# main.net
KiCad netlist of a schematic drawn in EAGLE
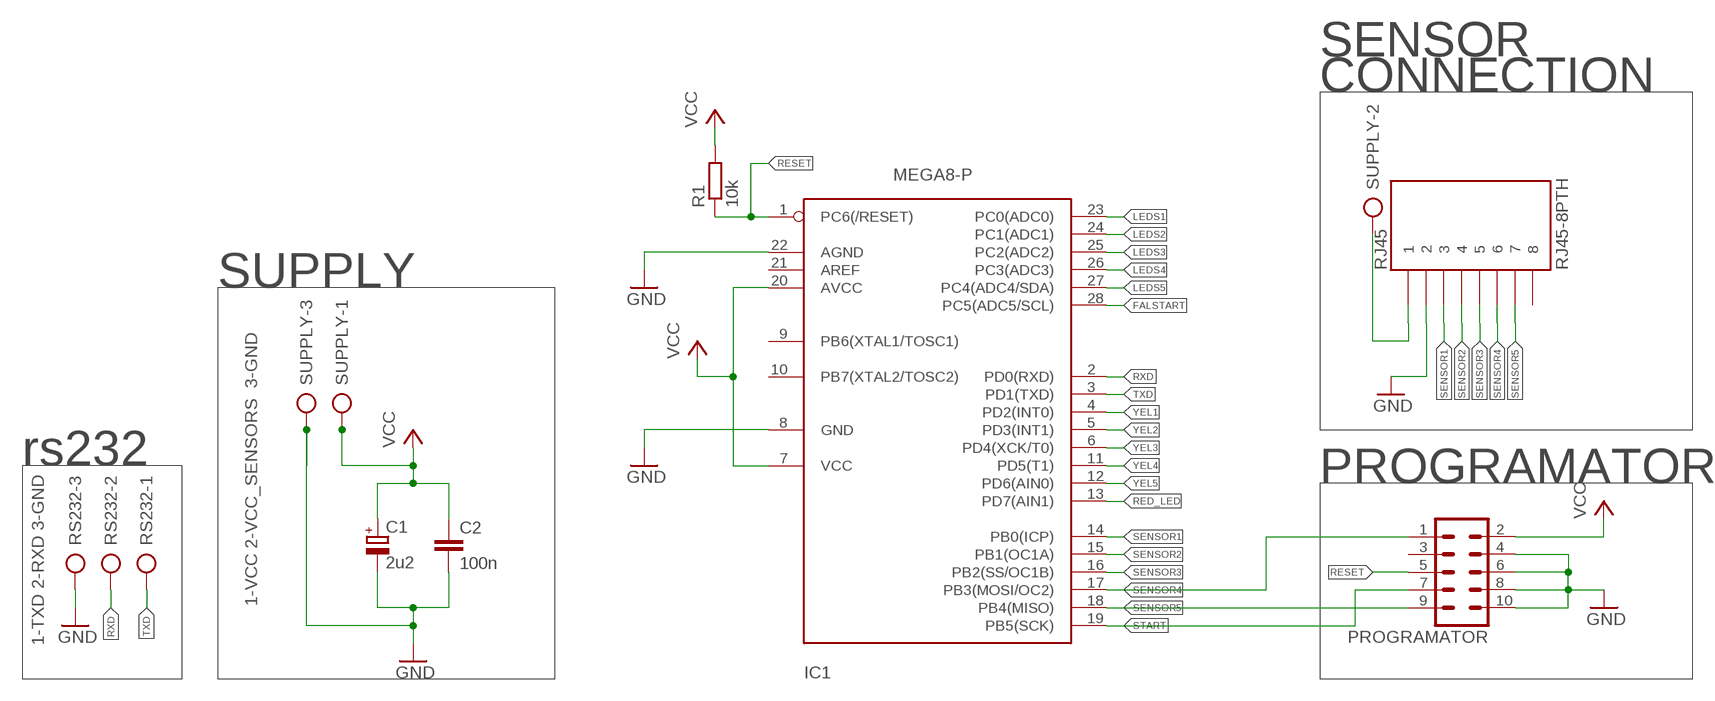
[diagram p0: schematic, sheet 1, part 1 of 2]
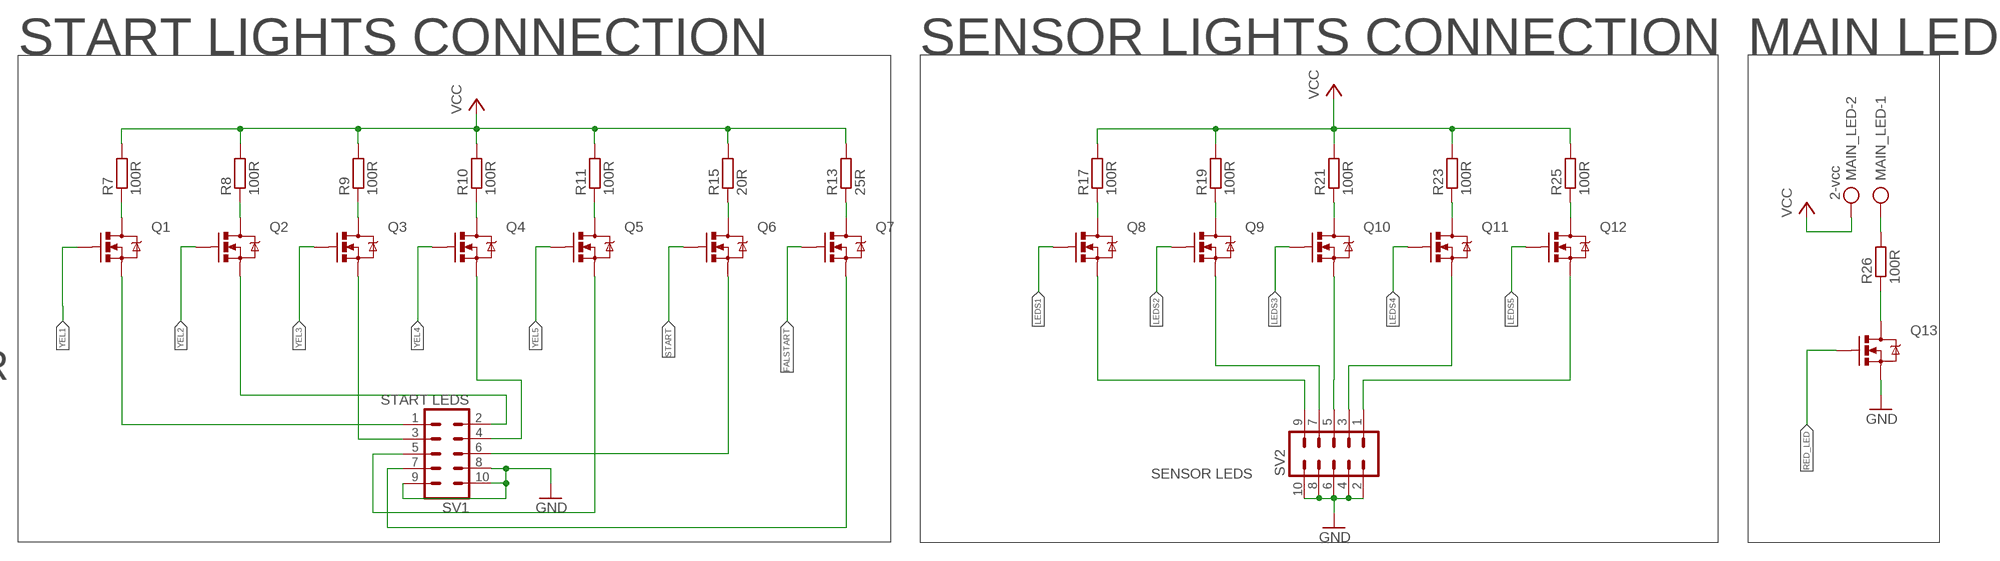
[diagram p1: schematic, sheet 1, part 2 of 2]

(export (version "E")
  (design (tool "Eeschema 10.0.6"))
  (components
    (comp (ref "C1")
      (value "2u2")
      (footprint "eagle-import:E2-5")
      (libsource (lib "eagle-import") (part "CPOL-EUE2-5"))
    )
    (comp (ref "C2")
      (value "100n")
      (footprint "eagle-import:C0805")
      (libsource (lib "eagle-import") (part "C-EUC0805"))
    )
    (comp (ref "IC1")
      (value "MEGA8-P")
      (footprint "eagle-import:DIL28-3")
      (libsource (lib "eagle-import") (part "MEGA8-P"))
    )
    (comp (ref "MAIN_LED")
      (value "2-vcc")
      (footprint "eagle-import:AK300_2")
      (libsource (lib "eagle-import") (part "AK300/2"))
    )
    (comp (ref "PROGRAMATOR")
      (value "ML10L")
      (footprint "eagle-import:ML10L")
      (libsource (lib "eagle-import") (part "ML10L"))
    )
    (comp (ref "Q1")
      (value "MOSFET-NCHANNEL2N7002PW")
      (footprint "eagle-import:SOT323")
      (libsource (lib "eagle-import") (part "MOSFET-NCHANNEL2N7002PW"))
    )
    (comp (ref "Q2")
      (value "MOSFET-NCHANNEL2N7002PW")
      (footprint "eagle-import:SOT323")
      (fields (field (name "PROD_ID") "TRANS-11151"))
      (libsource (lib "eagle-import") (part "MOSFET-NCHANNEL2N7002PW"))
    )
    (comp (ref "Q3")
      (value "MOSFET-NCHANNEL2N7002PW")
      (footprint "eagle-import:SOT323")
      (fields (field (name "PROD_ID") "TRANS-11151"))
      (libsource (lib "eagle-import") (part "MOSFET-NCHANNEL2N7002PW"))
    )
    (comp (ref "Q4")
      (value "MOSFET-NCHANNEL2N7002PW")
      (footprint "eagle-import:SOT323")
      (fields (field (name "PROD_ID") "TRANS-11151"))
      (libsource (lib "eagle-import") (part "MOSFET-NCHANNEL2N7002PW"))
    )
    (comp (ref "Q5")
      (value "MOSFET-NCHANNEL2N7002PW")
      (footprint "eagle-import:SOT323")
      (fields (field (name "PROD_ID") "TRANS-11151"))
      (libsource (lib "eagle-import") (part "MOSFET-NCHANNEL2N7002PW"))
    )
    (comp (ref "Q6")
      (value "MOSFET-NCHANNEL2N7002PW")
      (footprint "eagle-import:SOT323")
      (fields (field (name "PROD_ID") "TRANS-11151"))
      (libsource (lib "eagle-import") (part "MOSFET-NCHANNEL2N7002PW"))
    )
    (comp (ref "Q7")
      (value "MOSFET-NCHANNEL2N7002PW")
      (footprint "eagle-import:SOT323")
      (fields (field (name "PROD_ID") "TRANS-11151"))
      (libsource (lib "eagle-import") (part "MOSFET-NCHANNEL2N7002PW"))
    )
    (comp (ref "Q8")
      (value "MOSFET-NCHANNEL2N7002PW")
      (footprint "eagle-import:SOT323")
      (fields (field (name "PROD_ID") "TRANS-11151"))
      (libsource (lib "eagle-import") (part "MOSFET-NCHANNEL2N7002PW"))
    )
    (comp (ref "Q9")
      (value "MOSFET-NCHANNEL2N7002PW")
      (footprint "eagle-import:SOT323")
      (fields (field (name "PROD_ID") "TRANS-11151"))
      (libsource (lib "eagle-import") (part "MOSFET-NCHANNEL2N7002PW"))
    )
    (comp (ref "Q10")
      (value "MOSFET-NCHANNEL2N7002PW")
      (footprint "eagle-import:SOT323")
      (fields (field (name "PROD_ID") "TRANS-11151"))
      (libsource (lib "eagle-import") (part "MOSFET-NCHANNEL2N7002PW"))
    )
    (comp (ref "Q11")
      (value "MOSFET-NCHANNEL2N7002PW")
      (footprint "eagle-import:SOT323")
      (fields (field (name "PROD_ID") "TRANS-11151"))
      (libsource (lib "eagle-import") (part "MOSFET-NCHANNEL2N7002PW"))
    )
    (comp (ref "Q12")
      (value "MOSFET-NCHANNEL2N7002PW")
      (footprint "eagle-import:SOT323")
      (fields (field (name "PROD_ID") "TRANS-11151"))
      (libsource (lib "eagle-import") (part "MOSFET-NCHANNEL2N7002PW"))
    )
    (comp (ref "Q13")
      (value "MOSFET-NCHANNEL2N7002PW")
      (footprint "eagle-import:SOT323")
      (fields (field (name "PROD_ID") "TRANS-11151"))
      (libsource (lib "eagle-import") (part "MOSFET-NCHANNEL2N7002PW"))
    )
    (comp (ref "R1")
      (value "10k")
      (footprint "eagle-import:R0805")
      (libsource (lib "eagle-import") (part "R-EU_R0805"))
    )
    (comp (ref "R7")
      (value "100R")
      (footprint "eagle-import:R0805")
      (libsource (lib "eagle-import") (part "R-EU_R0805"))
    )
    (comp (ref "R8")
      (value "100R")
      (footprint "eagle-import:R0805")
      (libsource (lib "eagle-import") (part "R-EU_R0805"))
    )
    (comp (ref "R9")
      (value "100R")
      (footprint "eagle-import:R0805")
      (libsource (lib "eagle-import") (part "R-EU_R0805"))
    )
    (comp (ref "R10")
      (value "100R")
      (footprint "eagle-import:R0805")
      (libsource (lib "eagle-import") (part "R-EU_R0805"))
    )
    (comp (ref "R11")
      (value "100R")
      (footprint "eagle-import:R0805")
      (libsource (lib "eagle-import") (part "R-EU_R0805"))
    )
    (comp (ref "R13")
      (value "25R")
      (footprint "eagle-import:R0805")
      (libsource (lib "eagle-import") (part "R-EU_R0805"))
    )
    (comp (ref "R15")
      (value "20R")
      (footprint "eagle-import:R0805")
      (libsource (lib "eagle-import") (part "R-EU_R0805"))
    )
    (comp (ref "R17")
      (value "100R")
      (footprint "eagle-import:R0805")
      (libsource (lib "eagle-import") (part "R-EU_R0805"))
    )
    (comp (ref "R19")
      (value "100R")
      (footprint "eagle-import:R0805")
      (libsource (lib "eagle-import") (part "R-EU_R0805"))
    )
    (comp (ref "R21")
      (value "100R")
      (footprint "eagle-import:R0805")
      (libsource (lib "eagle-import") (part "R-EU_R0805"))
    )
    (comp (ref "R23")
      (value "100R")
      (footprint "eagle-import:R0805")
      (libsource (lib "eagle-import") (part "R-EU_R0805"))
    )
    (comp (ref "R25")
      (value "100R")
      (footprint "eagle-import:R0805")
      (libsource (lib "eagle-import") (part "R-EU_R0805"))
    )
    (comp (ref "R26")
      (value "100R")
      (footprint "eagle-import:R0805")
      (libsource (lib "eagle-import") (part "R-EU_R0805"))
    )
    (comp (ref "RJ45")
      (value "RJ45-8PTH")
      (footprint "eagle-import:RJ45-8")
      (libsource (lib "eagle-import") (part "RJ45-8PTH"))
    )
    (comp (ref "RS232")
      (value "1-TXD 2-RXD 3-GND")
      (footprint "eagle-import:AK300_3")
      (libsource (lib "eagle-import") (part "AK300/3"))
    )
    (comp (ref "SUPPLY")
      (value "1-VCC 2-VCC_SENSORS 3-GND")
      (footprint "eagle-import:AK300_3")
      (libsource (lib "eagle-import") (part "AK300/3"))
    )
    (comp (ref "SV1")
      (value "START LEDS")
      (footprint "eagle-import:ML10")
      (libsource (lib "eagle-import") (part "ML10"))
    )
    (comp (ref "SV2")
      (value "SENSOR LEDS")
      (footprint "eagle-import:ML10")
      (libsource (lib "eagle-import") (part "ML10"))
    )
  )
  (nets
    (net (code "1") (name "FALSTART") (class "Default")
      (node (ref "IC1") (pin "28") (pinfunction "PC5(ADC5/SCL)_28") (pintype "bidirectional"))
      (node (ref "Q7") (pin "1") (pinfunction "G_1") (pintype "passive"))
    )
    (net (code "2") (name "GND") (class "Default")
      (node (ref "C1") (pin "-") (pinfunction "-_-") (pintype "passive"))
      (node (ref "C2") (pin "2") (pinfunction "2_2") (pintype "passive"))
      (node (ref "IC1") (pin "22") (pinfunction "AGND_22") (pintype "bidirectional"))
      (node (ref "IC1") (pin "8") (pinfunction "GND_8") (pintype "bidirectional"))
      (node (ref "PROGRAMATOR") (pin "10") (pinfunction "10_10") (pintype "passive"))
      (node (ref "PROGRAMATOR") (pin "4") (pinfunction "4_4") (pintype "passive"))
      (node (ref "PROGRAMATOR") (pin "6") (pinfunction "6_6") (pintype "passive"))
      (node (ref "PROGRAMATOR") (pin "8") (pinfunction "8_8") (pintype "passive"))
      (node (ref "Q13") (pin "2") (pinfunction "S_2") (pintype "passive"))
      (node (ref "RJ45") (pin "2") (pinfunction "2_2") (pintype "bidirectional"))
      (node (ref "RS232") (pin "3") (pinfunction "KL_3") (pintype "passive"))
      (node (ref "SUPPLY") (pin "3") (pinfunction "KL_3") (pintype "passive"))
      (node (ref "SV1") (pin "10") (pinfunction "10_10") (pintype "passive"))
      (node (ref "SV1") (pin "8") (pinfunction "8_8") (pintype "passive"))
      (node (ref "SV1") (pin "9") (pinfunction "9_9") (pintype "passive"))
      (node (ref "SV2") (pin "10") (pinfunction "10_10") (pintype "passive"))
      (node (ref "SV2") (pin "2") (pinfunction "2_2") (pintype "passive"))
      (node (ref "SV2") (pin "4") (pinfunction "4_4") (pintype "passive"))
      (node (ref "SV2") (pin "6") (pinfunction "6_6") (pintype "passive"))
      (node (ref "SV2") (pin "8") (pinfunction "8_8") (pintype "passive"))
    )
    (net (code "3") (name "LEDS1") (class "Default")
      (node (ref "IC1") (pin "23") (pinfunction "PC0(ADC0)_23") (pintype "bidirectional"))
      (node (ref "Q8") (pin "1") (pinfunction "G_1") (pintype "passive"))
    )
    (net (code "4") (name "LEDS2") (class "Default")
      (node (ref "IC1") (pin "24") (pinfunction "PC1(ADC1)_24") (pintype "bidirectional"))
      (node (ref "Q9") (pin "1") (pinfunction "G_1") (pintype "passive"))
    )
    (net (code "5") (name "LEDS3") (class "Default")
      (node (ref "IC1") (pin "25") (pinfunction "PC2(ADC2)_25") (pintype "bidirectional"))
      (node (ref "Q10") (pin "1") (pinfunction "G_1") (pintype "passive"))
    )
    (net (code "6") (name "LEDS4") (class "Default")
      (node (ref "IC1") (pin "26") (pinfunction "PC3(ADC3)_26") (pintype "bidirectional"))
      (node (ref "Q11") (pin "1") (pinfunction "G_1") (pintype "passive"))
    )
    (net (code "7") (name "LEDS5") (class "Default")
      (node (ref "IC1") (pin "27") (pinfunction "PC4(ADC4/SDA)_27") (pintype "bidirectional"))
      (node (ref "Q12") (pin "1") (pinfunction "G_1") (pintype "passive"))
    )
    (net (code "8") (name "Net-(MAIN_LEDA-KL)") (class "Default")
      (node (ref "MAIN_LED") (pin "1") (pinfunction "KL_1") (pintype "passive"))
      (node (ref "R26") (pin "2") (pinfunction "2_2") (pintype "passive"))
    )
    (net (code "9") (name "Net-(Q1-D)") (class "Default")
      (node (ref "Q1") (pin "3") (pinfunction "D_3") (pintype "passive"))
      (node (ref "R7") (pin "1") (pinfunction "1_1") (pintype "passive"))
    )
    (net (code "10") (name "Net-(Q1-S)") (class "Default")
      (node (ref "Q1") (pin "2") (pinfunction "S_2") (pintype "passive"))
      (node (ref "SV1") (pin "1") (pinfunction "1_1") (pintype "passive"))
    )
    (net (code "11") (name "Net-(Q2-D)") (class "Default")
      (node (ref "Q2") (pin "3") (pinfunction "D_3") (pintype "passive"))
      (node (ref "R8") (pin "1") (pinfunction "1_1") (pintype "passive"))
    )
    (net (code "12") (name "Net-(Q2-S)") (class "Default")
      (node (ref "Q2") (pin "2") (pinfunction "S_2") (pintype "passive"))
      (node (ref "SV1") (pin "2") (pinfunction "2_2") (pintype "passive"))
    )
    (net (code "13") (name "Net-(Q3-D)") (class "Default")
      (node (ref "Q3") (pin "3") (pinfunction "D_3") (pintype "passive"))
      (node (ref "R9") (pin "1") (pinfunction "1_1") (pintype "passive"))
    )
    (net (code "14") (name "Net-(Q3-S)") (class "Default")
      (node (ref "Q3") (pin "2") (pinfunction "S_2") (pintype "passive"))
      (node (ref "SV1") (pin "3") (pinfunction "3_3") (pintype "passive"))
    )
    (net (code "15") (name "Net-(Q4-D)") (class "Default")
      (node (ref "Q4") (pin "3") (pinfunction "D_3") (pintype "passive"))
      (node (ref "R10") (pin "1") (pinfunction "1_1") (pintype "passive"))
    )
    (net (code "16") (name "Net-(Q4-S)") (class "Default")
      (node (ref "Q4") (pin "2") (pinfunction "S_2") (pintype "passive"))
      (node (ref "SV1") (pin "4") (pinfunction "4_4") (pintype "passive"))
    )
    (net (code "17") (name "Net-(Q5-D)") (class "Default")
      (node (ref "Q5") (pin "3") (pinfunction "D_3") (pintype "passive"))
      (node (ref "R11") (pin "1") (pinfunction "1_1") (pintype "passive"))
    )
    (net (code "18") (name "Net-(Q5-S)") (class "Default")
      (node (ref "Q5") (pin "2") (pinfunction "S_2") (pintype "passive"))
      (node (ref "SV1") (pin "5") (pinfunction "5_5") (pintype "passive"))
    )
    (net (code "19") (name "Net-(Q6-D)") (class "Default")
      (node (ref "Q6") (pin "3") (pinfunction "D_3") (pintype "passive"))
      (node (ref "R15") (pin "1") (pinfunction "1_1") (pintype "passive"))
    )
    (net (code "20") (name "Net-(Q6-S)") (class "Default")
      (node (ref "Q6") (pin "2") (pinfunction "S_2") (pintype "passive"))
      (node (ref "SV1") (pin "6") (pinfunction "6_6") (pintype "passive"))
    )
    (net (code "21") (name "Net-(Q7-D)") (class "Default")
      (node (ref "Q7") (pin "3") (pinfunction "D_3") (pintype "passive"))
      (node (ref "R13") (pin "1") (pinfunction "1_1") (pintype "passive"))
    )
    (net (code "22") (name "Net-(Q7-S)") (class "Default")
      (node (ref "Q7") (pin "2") (pinfunction "S_2") (pintype "passive"))
      (node (ref "SV1") (pin "7") (pinfunction "7_7") (pintype "passive"))
    )
    (net (code "23") (name "Net-(Q8-D)") (class "Default")
      (node (ref "Q8") (pin "3") (pinfunction "D_3") (pintype "passive"))
      (node (ref "R17") (pin "1") (pinfunction "1_1") (pintype "passive"))
    )
    (net (code "24") (name "Net-(Q8-S)") (class "Default")
      (node (ref "Q8") (pin "2") (pinfunction "S_2") (pintype "passive"))
      (node (ref "SV2") (pin "9") (pinfunction "9_9") (pintype "passive"))
    )
    (net (code "25") (name "Net-(Q9-D)") (class "Default")
      (node (ref "Q9") (pin "3") (pinfunction "D_3") (pintype "passive"))
      (node (ref "R19") (pin "1") (pinfunction "1_1") (pintype "passive"))
    )
    (net (code "26") (name "Net-(Q9-S)") (class "Default")
      (node (ref "Q9") (pin "2") (pinfunction "S_2") (pintype "passive"))
      (node (ref "SV2") (pin "7") (pinfunction "7_7") (pintype "passive"))
    )
    (net (code "27") (name "Net-(Q10-D)") (class "Default")
      (node (ref "Q10") (pin "3") (pinfunction "D_3") (pintype "passive"))
      (node (ref "R21") (pin "1") (pinfunction "1_1") (pintype "passive"))
    )
    (net (code "28") (name "Net-(Q10-S)") (class "Default")
      (node (ref "Q10") (pin "2") (pinfunction "S_2") (pintype "passive"))
      (node (ref "SV2") (pin "5") (pinfunction "5_5") (pintype "passive"))
    )
    (net (code "29") (name "Net-(Q11-D)") (class "Default")
      (node (ref "Q11") (pin "3") (pinfunction "D_3") (pintype "passive"))
      (node (ref "R23") (pin "1") (pinfunction "1_1") (pintype "passive"))
    )
    (net (code "30") (name "Net-(Q11-S)") (class "Default")
      (node (ref "Q11") (pin "2") (pinfunction "S_2") (pintype "passive"))
      (node (ref "SV2") (pin "3") (pinfunction "3_3") (pintype "passive"))
    )
    (net (code "31") (name "Net-(Q12-D)") (class "Default")
      (node (ref "Q12") (pin "3") (pinfunction "D_3") (pintype "passive"))
      (node (ref "R25") (pin "1") (pinfunction "1_1") (pintype "passive"))
    )
    (net (code "32") (name "Net-(Q12-S)") (class "Default")
      (node (ref "Q12") (pin "2") (pinfunction "S_2") (pintype "passive"))
      (node (ref "SV2") (pin "1") (pinfunction "1_1") (pintype "passive"))
    )
    (net (code "33") (name "Net-(Q13-D)") (class "Default")
      (node (ref "Q13") (pin "3") (pinfunction "D_3") (pintype "passive"))
      (node (ref "R26") (pin "1") (pinfunction "1_1") (pintype "passive"))
    )
    (net (code "34") (name "Net-(SUPPLYB-KL)") (class "Default")
      (node (ref "RJ45") (pin "1") (pinfunction "1_1") (pintype "bidirectional"))
      (node (ref "SUPPLY") (pin "2") (pinfunction "KL_2") (pintype "passive"))
    )
    (net (code "35") (name "RED_LED") (class "Default")
      (node (ref "IC1") (pin "13") (pinfunction "PD7(AIN1)_13") (pintype "bidirectional"))
      (node (ref "Q13") (pin "1") (pinfunction "G_1") (pintype "passive"))
    )
    (net (code "36") (name "RESET") (class "Default")
      (node (ref "IC1") (pin "1") (pinfunction "PC6(/RESET)_1") (pintype "bidirectional"))
      (node (ref "PROGRAMATOR") (pin "5") (pinfunction "5_5") (pintype "passive"))
      (node (ref "R1") (pin "1") (pinfunction "1_1") (pintype "passive"))
    )
    (net (code "37") (name "RXD") (class "Default")
      (node (ref "IC1") (pin "2") (pinfunction "PD0(RXD)_2") (pintype "bidirectional"))
      (node (ref "RS232") (pin "2") (pinfunction "KL_2") (pintype "passive"))
    )
    (net (code "38") (name "SENSOR1") (class "Default")
      (node (ref "IC1") (pin "14") (pinfunction "PB0(ICP)_14") (pintype "bidirectional"))
      (node (ref "RJ45") (pin "3") (pinfunction "3_3") (pintype "bidirectional"))
    )
    (net (code "39") (name "SENSOR2") (class "Default")
      (node (ref "IC1") (pin "15") (pinfunction "PB1(OC1A)_15") (pintype "bidirectional"))
      (node (ref "RJ45") (pin "4") (pinfunction "4_4") (pintype "bidirectional"))
    )
    (net (code "40") (name "SENSOR3") (class "Default")
      (node (ref "IC1") (pin "16") (pinfunction "PB2(SS/OC1B)_16") (pintype "bidirectional"))
      (node (ref "RJ45") (pin "5") (pinfunction "5_5") (pintype "bidirectional"))
    )
    (net (code "41") (name "SENSOR4") (class "Default")
      (node (ref "IC1") (pin "17") (pinfunction "PB3(MOSI/OC2)_17") (pintype "bidirectional"))
      (node (ref "PROGRAMATOR") (pin "1") (pinfunction "1_1") (pintype "passive"))
      (node (ref "RJ45") (pin "6") (pinfunction "6_6") (pintype "bidirectional"))
    )
    (net (code "42") (name "SENSOR5") (class "Default")
      (node (ref "IC1") (pin "18") (pinfunction "PB4(MISO)_18") (pintype "bidirectional"))
      (node (ref "PROGRAMATOR") (pin "9") (pinfunction "9_9") (pintype "passive"))
      (node (ref "RJ45") (pin "7") (pinfunction "7_7") (pintype "bidirectional"))
    )
    (net (code "43") (name "START") (class "Default")
      (node (ref "IC1") (pin "19") (pinfunction "PB5(SCK)_19") (pintype "bidirectional"))
      (node (ref "PROGRAMATOR") (pin "7") (pinfunction "7_7") (pintype "passive"))
      (node (ref "Q6") (pin "1") (pinfunction "G_1") (pintype "passive"))
    )
    (net (code "44") (name "TXD") (class "Default")
      (node (ref "IC1") (pin "3") (pinfunction "PD1(TXD)_3") (pintype "bidirectional"))
      (node (ref "RS232") (pin "1") (pinfunction "KL_1") (pintype "passive"))
    )
    (net (code "45") (name "VCC") (class "Default")
      (node (ref "C1") (pin "+") (pinfunction "+_+") (pintype "passive"))
      (node (ref "C2") (pin "1") (pinfunction "1_1") (pintype "passive"))
      (node (ref "IC1") (pin "20") (pinfunction "AVCC_20") (pintype "bidirectional"))
      (node (ref "IC1") (pin "7") (pinfunction "VCC_7") (pintype "bidirectional"))
      (node (ref "MAIN_LED") (pin "2") (pinfunction "KL_2") (pintype "passive"))
      (node (ref "PROGRAMATOR") (pin "2") (pinfunction "2_2") (pintype "passive"))
      (node (ref "R1") (pin "2") (pinfunction "2_2") (pintype "passive"))
      (node (ref "R10") (pin "2") (pinfunction "2_2") (pintype "passive"))
      (node (ref "R11") (pin "2") (pinfunction "2_2") (pintype "passive"))
      (node (ref "R13") (pin "2") (pinfunction "2_2") (pintype "passive"))
      (node (ref "R15") (pin "2") (pinfunction "2_2") (pintype "passive"))
      (node (ref "R17") (pin "2") (pinfunction "2_2") (pintype "passive"))
      (node (ref "R19") (pin "2") (pinfunction "2_2") (pintype "passive"))
      (node (ref "R21") (pin "2") (pinfunction "2_2") (pintype "passive"))
      (node (ref "R23") (pin "2") (pinfunction "2_2") (pintype "passive"))
      (node (ref "R25") (pin "2") (pinfunction "2_2") (pintype "passive"))
      (node (ref "R7") (pin "2") (pinfunction "2_2") (pintype "passive"))
      (node (ref "R8") (pin "2") (pinfunction "2_2") (pintype "passive"))
      (node (ref "R9") (pin "2") (pinfunction "2_2") (pintype "passive"))
      (node (ref "SUPPLY") (pin "1") (pinfunction "KL_1") (pintype "passive"))
    )
    (net (code "46") (name "YEL1") (class "Default")
      (node (ref "IC1") (pin "4") (pinfunction "PD2(INT0)_4") (pintype "bidirectional"))
      (node (ref "Q1") (pin "1") (pinfunction "G_1") (pintype "passive"))
    )
    (net (code "47") (name "YEL2") (class "Default")
      (node (ref "IC1") (pin "5") (pinfunction "PD3(INT1)_5") (pintype "bidirectional"))
      (node (ref "Q2") (pin "1") (pinfunction "G_1") (pintype "passive"))
    )
    (net (code "48") (name "YEL3") (class "Default")
      (node (ref "IC1") (pin "6") (pinfunction "PD4(XCK/T0)_6") (pintype "bidirectional"))
      (node (ref "Q3") (pin "1") (pinfunction "G_1") (pintype "passive"))
    )
    (net (code "49") (name "YEL4") (class "Default")
      (node (ref "IC1") (pin "11") (pinfunction "PD5(T1)_11") (pintype "bidirectional"))
      (node (ref "Q4") (pin "1") (pinfunction "G_1") (pintype "passive"))
    )
    (net (code "50") (name "YEL5") (class "Default")
      (node (ref "IC1") (pin "12") (pinfunction "PD6(AIN0)_12") (pintype "bidirectional"))
      (node (ref "Q5") (pin "1") (pinfunction "G_1") (pintype "passive"))
    )
    (net (code "51") (name "unconnected-(IC1-AREF-Pad21)") (class "Default")
      (node (ref "IC1") (pin "21") (pinfunction "AREF_21") (pintype "bidirectional"))
    )
    (net (code "52") (name "unconnected-(IC1-PB6(XTAL1{slash}TOSC1)-Pad9)") (class "Default")
      (node (ref "IC1") (pin "9") (pinfunction "PB6(XTAL1/TOSC1)_9") (pintype "bidirectional"))
    )
    (net (code "53") (name "unconnected-(IC1-PB7(XTAL2{slash}TOSC2)-Pad10)") (class "Default")
      (node (ref "IC1") (pin "10") (pinfunction "PB7(XTAL2/TOSC2)_10") (pintype "bidirectional"))
    )
    (net (code "54") (name "unconnected-(PROGRAMATOR-Pad3)") (class "Default")
      (node (ref "PROGRAMATOR") (pin "3") (pinfunction "3_3") (pintype "passive"))
    )
    (net (code "55") (name "unconnected-(RJ45-Pad8)") (class "Default")
      (node (ref "RJ45") (pin "8") (pinfunction "8_8") (pintype "bidirectional"))
    )
  )
)
